# M1501B.net
KiCad netlist of a schematic drawn in EAGLE
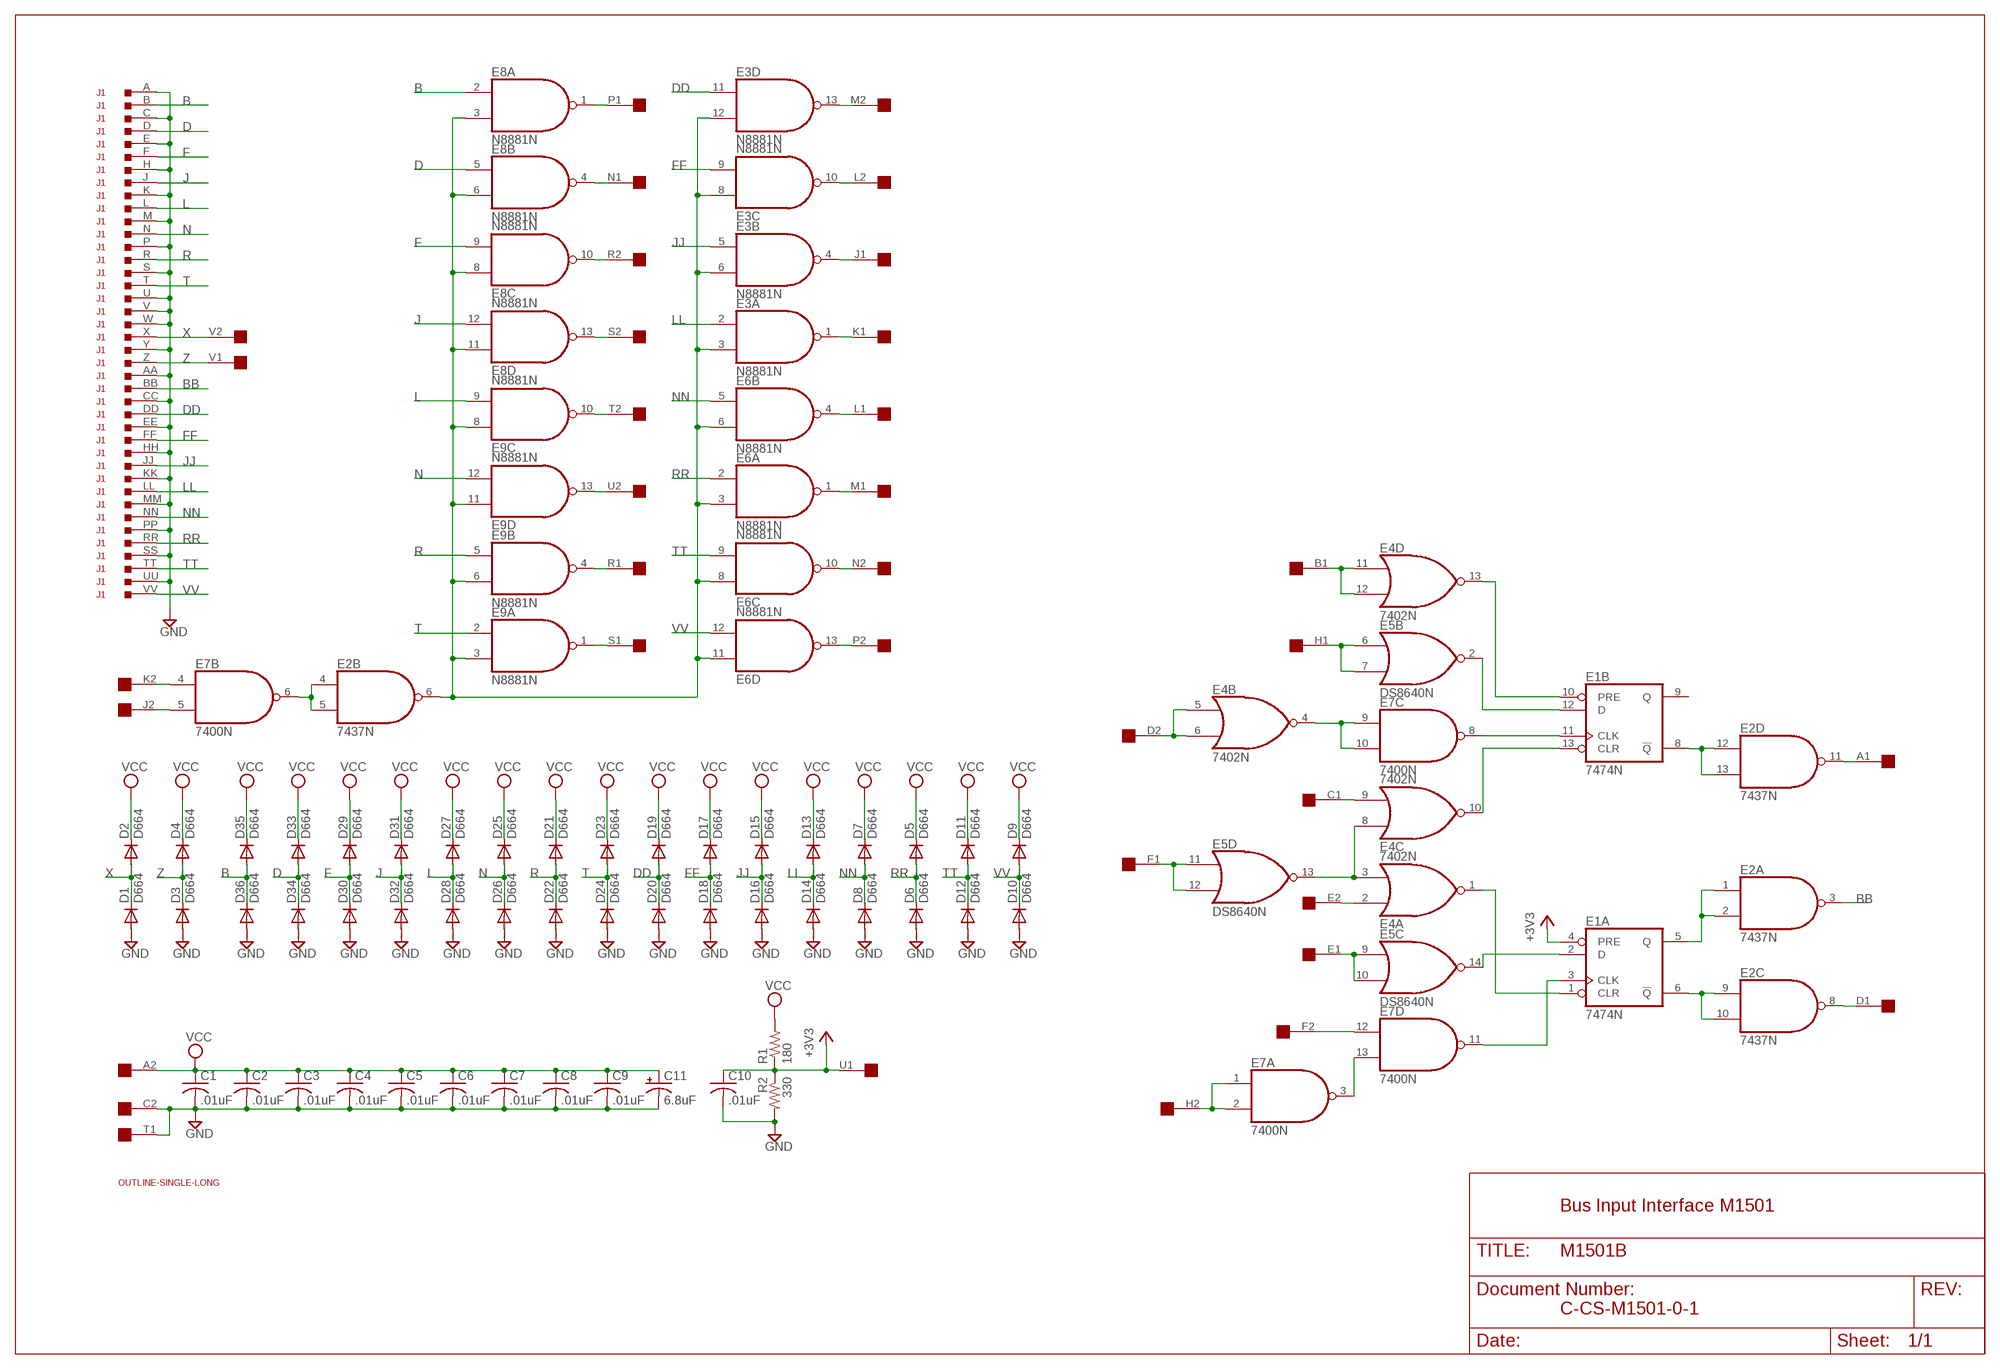
[diagram p0: schematic, sheet 1]

(export (version "E")
  (design (tool "Eeschema 10.0.6"))
  (components
    (comp (ref "C1")
      (value ".01uF")
      (footprint "eagle-import:C050-025X075")
      (libsource (lib "eagle-import") (part "C-US050-025X075"))
    )
    (comp (ref "C2")
      (value ".01uF")
      (footprint "eagle-import:C050-025X075")
      (libsource (lib "eagle-import") (part "C-US050-025X075"))
    )
    (comp (ref "C3")
      (value ".01uF")
      (footprint "eagle-import:C050-025X075")
      (libsource (lib "eagle-import") (part "C-US050-025X075"))
    )
    (comp (ref "C4")
      (value ".01uF")
      (footprint "eagle-import:C050-025X075")
      (libsource (lib "eagle-import") (part "C-US050-025X075"))
    )
    (comp (ref "C5")
      (value ".01uF")
      (footprint "eagle-import:C050-025X075")
      (libsource (lib "eagle-import") (part "C-US050-025X075"))
    )
    (comp (ref "C6")
      (value ".01uF")
      (footprint "eagle-import:C050-025X075")
      (libsource (lib "eagle-import") (part "C-US050-025X075"))
    )
    (comp (ref "C7")
      (value ".01uF")
      (footprint "eagle-import:C050-025X075")
      (libsource (lib "eagle-import") (part "C-US050-025X075"))
    )
    (comp (ref "C8")
      (value ".01uF")
      (footprint "eagle-import:C050-025X075")
      (libsource (lib "eagle-import") (part "C-US050-025X075"))
    )
    (comp (ref "C9")
      (value ".01uF")
      (footprint "eagle-import:C050-025X075")
      (libsource (lib "eagle-import") (part "C-US050-025X075"))
    )
    (comp (ref "C10")
      (value ".01uF")
      (footprint "eagle-import:C050-025X075")
      (libsource (lib "eagle-import") (part "C-US050-025X075"))
    )
    (comp (ref "C11")
      (value "6.8uF")
      (footprint "eagle-import:E12-8")
      (libsource (lib "eagle-import") (part "CPOL-USE20-8AXIAL"))
    )
    (comp (ref "D1")
      (value "D664")
      (footprint "eagle-import:DO35-10")
      (libsource (lib "eagle-import") (part "DIODE-DO35-10"))
    )
    (comp (ref "D2")
      (value "D664")
      (footprint "eagle-import:DO35-10")
      (libsource (lib "eagle-import") (part "DIODE-DO35-10"))
    )
    (comp (ref "D3")
      (value "D664")
      (footprint "eagle-import:DO35-10")
      (libsource (lib "eagle-import") (part "DIODE-DO35-10"))
    )
    (comp (ref "D4")
      (value "D664")
      (footprint "eagle-import:DO35-10")
      (libsource (lib "eagle-import") (part "DIODE-DO35-10"))
    )
    (comp (ref "D5")
      (value "D664")
      (footprint "eagle-import:DO35-10")
      (libsource (lib "eagle-import") (part "DIODE-DO35-10"))
    )
    (comp (ref "D6")
      (value "D664")
      (footprint "eagle-import:DO35-10")
      (libsource (lib "eagle-import") (part "DIODE-DO35-10"))
    )
    (comp (ref "D7")
      (value "D664")
      (footprint "eagle-import:DO35-10")
      (libsource (lib "eagle-import") (part "DIODE-DO35-10"))
    )
    (comp (ref "D8")
      (value "D664")
      (footprint "eagle-import:DO35-10")
      (libsource (lib "eagle-import") (part "DIODE-DO35-10"))
    )
    (comp (ref "D9")
      (value "D664")
      (footprint "eagle-import:DO35-10")
      (libsource (lib "eagle-import") (part "DIODE-DO35-10"))
    )
    (comp (ref "D10")
      (value "D664")
      (footprint "eagle-import:DO35-10")
      (libsource (lib "eagle-import") (part "DIODE-DO35-10"))
    )
    (comp (ref "D11")
      (value "D664")
      (footprint "eagle-import:DO35-10")
      (libsource (lib "eagle-import") (part "DIODE-DO35-10"))
    )
    (comp (ref "D12")
      (value "D664")
      (footprint "eagle-import:DO35-10")
      (libsource (lib "eagle-import") (part "DIODE-DO35-10"))
    )
    (comp (ref "D13")
      (value "D664")
      (footprint "eagle-import:DO35-10")
      (libsource (lib "eagle-import") (part "DIODE-DO35-10"))
    )
    (comp (ref "D14")
      (value "D664")
      (footprint "eagle-import:DO35-10")
      (libsource (lib "eagle-import") (part "DIODE-DO35-10"))
    )
    (comp (ref "D15")
      (value "D664")
      (footprint "eagle-import:DO35-10")
      (libsource (lib "eagle-import") (part "DIODE-DO35-10"))
    )
    (comp (ref "D16")
      (value "D664")
      (footprint "eagle-import:DO35-10")
      (libsource (lib "eagle-import") (part "DIODE-DO35-10"))
    )
    (comp (ref "D17")
      (value "D664")
      (footprint "eagle-import:DO35-10")
      (libsource (lib "eagle-import") (part "DIODE-DO35-10"))
    )
    (comp (ref "D18")
      (value "D664")
      (footprint "eagle-import:DO35-10")
      (libsource (lib "eagle-import") (part "DIODE-DO35-10"))
    )
    (comp (ref "D19")
      (value "D664")
      (footprint "eagle-import:DO35-10")
      (libsource (lib "eagle-import") (part "DIODE-DO35-10"))
    )
    (comp (ref "D20")
      (value "D664")
      (footprint "eagle-import:DO35-10")
      (libsource (lib "eagle-import") (part "DIODE-DO35-10"))
    )
    (comp (ref "D21")
      (value "D664")
      (footprint "eagle-import:DO35-10")
      (libsource (lib "eagle-import") (part "DIODE-DO35-10"))
    )
    (comp (ref "D22")
      (value "D664")
      (footprint "eagle-import:DO35-10")
      (libsource (lib "eagle-import") (part "DIODE-DO35-10"))
    )
    (comp (ref "D23")
      (value "D664")
      (footprint "eagle-import:DO35-10")
      (libsource (lib "eagle-import") (part "DIODE-DO35-10"))
    )
    (comp (ref "D24")
      (value "D664")
      (footprint "eagle-import:DO35-10")
      (libsource (lib "eagle-import") (part "DIODE-DO35-10"))
    )
    (comp (ref "D25")
      (value "D664")
      (footprint "eagle-import:DO35-10")
      (libsource (lib "eagle-import") (part "DIODE-DO35-10"))
    )
    (comp (ref "D26")
      (value "D664")
      (footprint "eagle-import:DO35-10")
      (libsource (lib "eagle-import") (part "DIODE-DO35-10"))
    )
    (comp (ref "D27")
      (value "D664")
      (footprint "eagle-import:DO35-10")
      (libsource (lib "eagle-import") (part "DIODE-DO35-10"))
    )
    (comp (ref "D28")
      (value "D664")
      (footprint "eagle-import:DO35-10")
      (libsource (lib "eagle-import") (part "DIODE-DO35-10"))
    )
    (comp (ref "D29")
      (value "D664")
      (footprint "eagle-import:DO35-10")
      (libsource (lib "eagle-import") (part "DIODE-DO35-10"))
    )
    (comp (ref "D30")
      (value "D664")
      (footprint "eagle-import:DO35-10")
      (libsource (lib "eagle-import") (part "DIODE-DO35-10"))
    )
    (comp (ref "D31")
      (value "D664")
      (footprint "eagle-import:DO35-10")
      (libsource (lib "eagle-import") (part "DIODE-DO35-10"))
    )
    (comp (ref "D32")
      (value "D664")
      (footprint "eagle-import:DO35-10")
      (libsource (lib "eagle-import") (part "DIODE-DO35-10"))
    )
    (comp (ref "D33")
      (value "D664")
      (footprint "eagle-import:DO35-10")
      (libsource (lib "eagle-import") (part "DIODE-DO35-10"))
    )
    (comp (ref "D34")
      (value "D664")
      (footprint "eagle-import:DO35-10")
      (libsource (lib "eagle-import") (part "DIODE-DO35-10"))
    )
    (comp (ref "D35")
      (value "D664")
      (footprint "eagle-import:DO35-10")
      (libsource (lib "eagle-import") (part "DIODE-DO35-10"))
    )
    (comp (ref "D36")
      (value "D664")
      (footprint "eagle-import:DO35-10")
      (libsource (lib "eagle-import") (part "DIODE-DO35-10"))
    )
    (comp (ref "E1")
      (value "7474N")
      (footprint "eagle-import:DIL14")
      (libsource (lib "eagle-import") (part "7474NS"))
    )
    (comp (ref "E2")
      (value "7437N")
      (footprint "eagle-import:DIL14")
      (libsource (lib "eagle-import") (part "7437N"))
    )
    (comp (ref "E3")
      (value "N8881N")
      (footprint "eagle-import:DIL14")
      (libsource (lib "eagle-import") (part "N8881N"))
    )
    (comp (ref "E4")
      (value "7402N")
      (footprint "eagle-import:DIL14")
      (libsource (lib "eagle-import") (part "7402N"))
    )
    (comp (ref "E5")
      (value "DS8640N")
      (footprint "eagle-import:DIL14")
      (libsource (lib "eagle-import") (part "DS8640N"))
    )
    (comp (ref "E6")
      (value "N8881N")
      (footprint "eagle-import:DIL14")
      (libsource (lib "eagle-import") (part "N8881N"))
    )
    (comp (ref "E7")
      (value "7400N")
      (footprint "eagle-import:DIL14")
      (libsource (lib "eagle-import") (part "7400N"))
    )
    (comp (ref "E8")
      (value "N8881N")
      (footprint "eagle-import:DIL14")
      (libsource (lib "eagle-import") (part "N8881N"))
    )
    (comp (ref "E9")
      (value "N8881N")
      (footprint "eagle-import:DIL14")
      (libsource (lib "eagle-import") (part "N8881N"))
    )
    (comp (ref "J1")
      (value "DEC40PINSH")
      (footprint "eagle-import:DEC40PINH")
      (libsource (lib "eagle-import") (part "DEC40PINSH"))
    )
    (comp (ref "R1")
      (value "180")
      (footprint "eagle-import:0207_10")
      (libsource (lib "eagle-import") (part "R-US_0207/10"))
    )
    (comp (ref "R2")
      (value "330")
      (footprint "eagle-import:0207_10")
      (libsource (lib "eagle-import") (part "R-US_0207/10"))
    )
    (comp (ref "U$1")
      (value "OUTLINE-SINGLE-LONG")
      (footprint "eagle-import:SINGLE-LONG")
      (libsource (lib "eagle-import") (part "OUTLINE-SINGLE-LONG"))
    )
    (comp (ref "U$2")
      (value "SINGLE")
      (footprint "eagle-import:EDGE-CON2")
      (libsource (lib "eagle-import") (part "SINGLE"))
    )
  )
  (nets
    (net (code "1") (name "+3V3") (class "Default")
      (node (ref "C10") (pin "1") (pinfunction "1_1") (pintype "passive"))
      (node (ref "E1") (pin "4") (pinfunction "PRE_4") (pintype "input"))
      (node (ref "R1") (pin "1") (pinfunction "1_1") (pintype "passive"))
      (node (ref "R2") (pin "1") (pinfunction "1_1") (pintype "passive"))
      (node (ref "U$2") (pin "U1") (pinfunction "1_U1") (pintype "bidirectional"))
    )
    (net (code "2") (name "/B") (class "Default")
      (node (ref "D35") (pin "A") (pinfunction "A_A") (pintype "passive"))
      (node (ref "D36") (pin "C") (pinfunction "C_C") (pintype "passive"))
      (node (ref "E8") (pin "2") (pinfunction "I0_2") (pintype "input"))
      (node (ref "J1") (pin "B") (pinfunction "P$2_B") (pintype "passive"))
    )
    (net (code "3") (name "/BB") (class "Default")
      (node (ref "E2") (pin "3") (pinfunction "O_3") (pintype "output"))
      (node (ref "J1") (pin "BB") (pinfunction "P$2_BB") (pintype "passive"))
    )
    (net (code "4") (name "/D") (class "Default")
      (node (ref "D33") (pin "A") (pinfunction "A_A") (pintype "passive"))
      (node (ref "D34") (pin "C") (pinfunction "C_C") (pintype "passive"))
      (node (ref "E8") (pin "5") (pinfunction "I0_5") (pintype "input"))
      (node (ref "J1") (pin "D") (pinfunction "P$2_D") (pintype "passive"))
    )
    (net (code "5") (name "/DD") (class "Default")
      (node (ref "D19") (pin "A") (pinfunction "A_A") (pintype "passive"))
      (node (ref "D20") (pin "C") (pinfunction "C_C") (pintype "passive"))
      (node (ref "E3") (pin "11") (pinfunction "I0_11") (pintype "input"))
      (node (ref "J1") (pin "DD") (pinfunction "P$2_DD") (pintype "passive"))
    )
    (net (code "6") (name "/F") (class "Default")
      (node (ref "D29") (pin "A") (pinfunction "A_A") (pintype "passive"))
      (node (ref "D30") (pin "C") (pinfunction "C_C") (pintype "passive"))
      (node (ref "E8") (pin "9") (pinfunction "I1_9") (pintype "input"))
      (node (ref "J1") (pin "F") (pinfunction "P$2_F") (pintype "passive"))
    )
    (net (code "7") (name "/FF") (class "Default")
      (node (ref "D17") (pin "A") (pinfunction "A_A") (pintype "passive"))
      (node (ref "D18") (pin "C") (pinfunction "C_C") (pintype "passive"))
      (node (ref "E3") (pin "9") (pinfunction "I1_9") (pintype "input"))
      (node (ref "J1") (pin "FF") (pinfunction "P$2_FF") (pintype "passive"))
    )
    (net (code "8") (name "/J") (class "Default")
      (node (ref "D31") (pin "A") (pinfunction "A_A") (pintype "passive"))
      (node (ref "D32") (pin "C") (pinfunction "C_C") (pintype "passive"))
      (node (ref "E8") (pin "12") (pinfunction "I1_12") (pintype "input"))
      (node (ref "J1") (pin "J") (pinfunction "P$2_J") (pintype "passive"))
    )
    (net (code "9") (name "/JJ") (class "Default")
      (node (ref "D15") (pin "A") (pinfunction "A_A") (pintype "passive"))
      (node (ref "D16") (pin "C") (pinfunction "C_C") (pintype "passive"))
      (node (ref "E3") (pin "5") (pinfunction "I0_5") (pintype "input"))
      (node (ref "J1") (pin "JJ") (pinfunction "P$2_JJ") (pintype "passive"))
    )
    (net (code "10") (name "/L") (class "Default")
      (node (ref "D27") (pin "A") (pinfunction "A_A") (pintype "passive"))
      (node (ref "D28") (pin "C") (pinfunction "C_C") (pintype "passive"))
      (node (ref "E9") (pin "9") (pinfunction "I1_9") (pintype "input"))
      (node (ref "J1") (pin "L") (pinfunction "P$2_L") (pintype "passive"))
    )
    (net (code "11") (name "/LL") (class "Default")
      (node (ref "D13") (pin "A") (pinfunction "A_A") (pintype "passive"))
      (node (ref "D14") (pin "C") (pinfunction "C_C") (pintype "passive"))
      (node (ref "E3") (pin "2") (pinfunction "I0_2") (pintype "input"))
      (node (ref "J1") (pin "LL") (pinfunction "P$2_LL") (pintype "passive"))
    )
    (net (code "12") (name "/N") (class "Default")
      (node (ref "D25") (pin "A") (pinfunction "A_A") (pintype "passive"))
      (node (ref "D26") (pin "C") (pinfunction "C_C") (pintype "passive"))
      (node (ref "E9") (pin "12") (pinfunction "I1_12") (pintype "input"))
      (node (ref "J1") (pin "N") (pinfunction "P$2_N") (pintype "passive"))
    )
    (net (code "13") (name "/NN") (class "Default")
      (node (ref "D7") (pin "A") (pinfunction "A_A") (pintype "passive"))
      (node (ref "D8") (pin "C") (pinfunction "C_C") (pintype "passive"))
      (node (ref "E6") (pin "5") (pinfunction "I0_5") (pintype "input"))
      (node (ref "J1") (pin "NN") (pinfunction "P$2_NN") (pintype "passive"))
    )
    (net (code "14") (name "/R") (class "Default")
      (node (ref "D21") (pin "A") (pinfunction "A_A") (pintype "passive"))
      (node (ref "D22") (pin "C") (pinfunction "C_C") (pintype "passive"))
      (node (ref "E9") (pin "5") (pinfunction "I0_5") (pintype "input"))
      (node (ref "J1") (pin "R") (pinfunction "P$2_R") (pintype "passive"))
    )
    (net (code "15") (name "/RR") (class "Default")
      (node (ref "D5") (pin "A") (pinfunction "A_A") (pintype "passive"))
      (node (ref "D6") (pin "C") (pinfunction "C_C") (pintype "passive"))
      (node (ref "E6") (pin "2") (pinfunction "I0_2") (pintype "input"))
      (node (ref "J1") (pin "RR") (pinfunction "P$2_RR") (pintype "passive"))
    )
    (net (code "16") (name "/T") (class "Default")
      (node (ref "D23") (pin "A") (pinfunction "A_A") (pintype "passive"))
      (node (ref "D24") (pin "C") (pinfunction "C_C") (pintype "passive"))
      (node (ref "E9") (pin "2") (pinfunction "I0_2") (pintype "input"))
      (node (ref "J1") (pin "T") (pinfunction "P$2_T") (pintype "passive"))
    )
    (net (code "17") (name "/TT") (class "Default")
      (node (ref "D11") (pin "A") (pinfunction "A_A") (pintype "passive"))
      (node (ref "D12") (pin "C") (pinfunction "C_C") (pintype "passive"))
      (node (ref "E6") (pin "9") (pinfunction "I1_9") (pintype "input"))
      (node (ref "J1") (pin "TT") (pinfunction "P$2_TT") (pintype "passive"))
    )
    (net (code "18") (name "/VV") (class "Default")
      (node (ref "D10") (pin "C") (pinfunction "C_C") (pintype "passive"))
      (node (ref "D9") (pin "A") (pinfunction "A_A") (pintype "passive"))
      (node (ref "E6") (pin "12") (pinfunction "I1_12") (pintype "input"))
      (node (ref "J1") (pin "VV") (pinfunction "P$2_VV") (pintype "passive"))
    )
    (net (code "19") (name "/X") (class "Default")
      (node (ref "D1") (pin "C") (pinfunction "C_C") (pintype "passive"))
      (node (ref "D2") (pin "A") (pinfunction "A_A") (pintype "passive"))
      (node (ref "J1") (pin "X") (pinfunction "P$2_X") (pintype "passive"))
      (node (ref "U$2") (pin "V2") (pinfunction "1_V2") (pintype "bidirectional"))
    )
    (net (code "20") (name "/Z") (class "Default")
      (node (ref "D3") (pin "C") (pinfunction "C_C") (pintype "passive"))
      (node (ref "D4") (pin "A") (pinfunction "A_A") (pintype "passive"))
      (node (ref "J1") (pin "Z") (pinfunction "P$2_Z") (pintype "passive"))
      (node (ref "U$2") (pin "V1") (pinfunction "1_V1") (pintype "bidirectional"))
    )
    (net (code "21") (name "GND") (class "Default")
      (node (ref "C1") (pin "2") (pinfunction "2_2") (pintype "passive"))
      (node (ref "C10") (pin "2") (pinfunction "2_2") (pintype "passive"))
      (node (ref "C11") (pin "-") (pinfunction "-_-") (pintype "passive"))
      (node (ref "C2") (pin "2") (pinfunction "2_2") (pintype "passive"))
      (node (ref "C3") (pin "2") (pinfunction "2_2") (pintype "passive"))
      (node (ref "C4") (pin "2") (pinfunction "2_2") (pintype "passive"))
      (node (ref "C5") (pin "2") (pinfunction "2_2") (pintype "passive"))
      (node (ref "C6") (pin "2") (pinfunction "2_2") (pintype "passive"))
      (node (ref "C7") (pin "2") (pinfunction "2_2") (pintype "passive"))
      (node (ref "C8") (pin "2") (pinfunction "2_2") (pintype "passive"))
      (node (ref "C9") (pin "2") (pinfunction "2_2") (pintype "passive"))
      (node (ref "D1") (pin "A") (pinfunction "A_A") (pintype "passive"))
      (node (ref "D10") (pin "A") (pinfunction "A_A") (pintype "passive"))
      (node (ref "D12") (pin "A") (pinfunction "A_A") (pintype "passive"))
      (node (ref "D14") (pin "A") (pinfunction "A_A") (pintype "passive"))
      (node (ref "D16") (pin "A") (pinfunction "A_A") (pintype "passive"))
      (node (ref "D18") (pin "A") (pinfunction "A_A") (pintype "passive"))
      (node (ref "D20") (pin "A") (pinfunction "A_A") (pintype "passive"))
      (node (ref "D22") (pin "A") (pinfunction "A_A") (pintype "passive"))
      (node (ref "D24") (pin "A") (pinfunction "A_A") (pintype "passive"))
      (node (ref "D26") (pin "A") (pinfunction "A_A") (pintype "passive"))
      (node (ref "D28") (pin "A") (pinfunction "A_A") (pintype "passive"))
      (node (ref "D3") (pin "A") (pinfunction "A_A") (pintype "passive"))
      (node (ref "D30") (pin "A") (pinfunction "A_A") (pintype "passive"))
      (node (ref "D32") (pin "A") (pinfunction "A_A") (pintype "passive"))
      (node (ref "D34") (pin "A") (pinfunction "A_A") (pintype "passive"))
      (node (ref "D36") (pin "A") (pinfunction "A_A") (pintype "passive"))
      (node (ref "D6") (pin "A") (pinfunction "A_A") (pintype "passive"))
      (node (ref "D8") (pin "A") (pinfunction "A_A") (pintype "passive"))
      (node (ref "J1") (pin "A") (pinfunction "P$2_A") (pintype "passive"))
      (node (ref "J1") (pin "AA") (pinfunction "P$2_AA") (pintype "passive"))
      (node (ref "J1") (pin "C") (pinfunction "P$2_C") (pintype "passive"))
      (node (ref "J1") (pin "CC") (pinfunction "P$2_CC") (pintype "passive"))
      (node (ref "J1") (pin "E") (pinfunction "P$2_E") (pintype "passive"))
      (node (ref "J1") (pin "EE") (pinfunction "P$2_EE") (pintype "passive"))
      (node (ref "J1") (pin "H") (pinfunction "P$2_H") (pintype "passive"))
      (node (ref "J1") (pin "HH") (pinfunction "P$2_HH") (pintype "passive"))
      (node (ref "J1") (pin "K") (pinfunction "P$2_K") (pintype "passive"))
      (node (ref "J1") (pin "KK") (pinfunction "P$2_KK") (pintype "passive"))
      (node (ref "J1") (pin "M") (pinfunction "P$2_M") (pintype "passive"))
      (node (ref "J1") (pin "MM") (pinfunction "P$2_MM") (pintype "passive"))
      (node (ref "J1") (pin "P") (pinfunction "P$2_P") (pintype "passive"))
      (node (ref "J1") (pin "PP") (pinfunction "P$2_PP") (pintype "passive"))
      (node (ref "J1") (pin "S") (pinfunction "P$2_S") (pintype "passive"))
      (node (ref "J1") (pin "SS") (pinfunction "P$2_SS") (pintype "passive"))
      (node (ref "J1") (pin "U") (pinfunction "P$2_U") (pintype "passive"))
      (node (ref "J1") (pin "UU") (pinfunction "P$2_UU") (pintype "passive"))
      (node (ref "J1") (pin "V") (pinfunction "P$2_V") (pintype "passive"))
      (node (ref "J1") (pin "W") (pinfunction "P$2_W") (pintype "passive"))
      (node (ref "J1") (pin "Y") (pinfunction "P$2_Y") (pintype "passive"))
      (node (ref "R2") (pin "2") (pinfunction "2_2") (pintype "passive"))
      (node (ref "U$2") (pin "C2") (pinfunction "1_C2") (pintype "bidirectional"))
      (node (ref "U$2") (pin "T1") (pinfunction "1_T1") (pintype "bidirectional"))
    )
    (net (code "22") (name "Net-(E1A-CLK)") (class "Default")
      (node (ref "E1") (pin "3") (pinfunction "CLK_3") (pintype "input"))
      (node (ref "E7") (pin "11") (pinfunction "O_11") (pintype "output"))
    )
    (net (code "23") (name "Net-(E1A-CLR)") (class "Default")
      (node (ref "E1") (pin "1") (pinfunction "CLR_1") (pintype "input"))
      (node (ref "E4") (pin "1") (pinfunction "O_1") (pintype "output"))
    )
    (net (code "24") (name "Net-(E1A-D)") (class "Default")
      (node (ref "E1") (pin "2") (pinfunction "D_2") (pintype "input"))
      (node (ref "E5") (pin "14") (pinfunction "O_14") (pintype "output"))
    )
    (net (code "25") (name "Net-(E1A-Q)") (class "Default")
      (node (ref "E1") (pin "5") (pinfunction "Q_5") (pintype "output"))
      (node (ref "E2") (pin "1") (pinfunction "I0_1") (pintype "input"))
      (node (ref "E2") (pin "2") (pinfunction "I1_2") (pintype "input"))
    )
    (net (code "26") (name "Net-(E1A-~{Q})") (class "Default")
      (node (ref "E1") (pin "6") (pinfunction "~{Q}_6") (pintype "output"))
      (node (ref "E2") (pin "10") (pinfunction "I1_10") (pintype "input"))
      (node (ref "E2") (pin "9") (pinfunction "I0_9") (pintype "input"))
    )
    (net (code "27") (name "Net-(E1B-CLK)") (class "Default")
      (node (ref "E1") (pin "11") (pinfunction "CLK_11") (pintype "input"))
      (node (ref "E7") (pin "8") (pinfunction "O_8") (pintype "output"))
    )
    (net (code "28") (name "Net-(E1B-CLR)") (class "Default")
      (node (ref "E1") (pin "13") (pinfunction "CLR_13") (pintype "input"))
      (node (ref "E4") (pin "10") (pinfunction "O_10") (pintype "output"))
    )
    (net (code "29") (name "Net-(E1B-D)") (class "Default")
      (node (ref "E1") (pin "12") (pinfunction "D_12") (pintype "input"))
      (node (ref "E5") (pin "2") (pinfunction "O_2") (pintype "output"))
    )
    (net (code "30") (name "Net-(E1B-PRE)") (class "Default")
      (node (ref "E1") (pin "10") (pinfunction "PRE_10") (pintype "input"))
      (node (ref "E4") (pin "13") (pinfunction "O_13") (pintype "output"))
    )
    (net (code "31") (name "Net-(E1B-~{Q})") (class "Default")
      (node (ref "E1") (pin "8") (pinfunction "~{Q}_8") (pintype "output"))
      (node (ref "E2") (pin "12") (pinfunction "I0_12") (pintype "input"))
      (node (ref "E2") (pin "13") (pinfunction "I1_13") (pintype "input"))
    )
    (net (code "32") (name "Net-(E2B-I0)") (class "Default")
      (node (ref "E2") (pin "4") (pinfunction "I0_4") (pintype "input"))
      (node (ref "E2") (pin "5") (pinfunction "I1_5") (pintype "input"))
      (node (ref "E7") (pin "6") (pinfunction "O_6") (pintype "output"))
    )
    (net (code "33") (name "Net-(E2B-O)") (class "Default")
      (node (ref "E2") (pin "6") (pinfunction "O_6") (pintype "output"))
      (node (ref "E3") (pin "12") (pinfunction "I1_12") (pintype "input"))
      (node (ref "E3") (pin "3") (pinfunction "I1_3") (pintype "input"))
      (node (ref "E3") (pin "6") (pinfunction "I1_6") (pintype "input"))
      (node (ref "E3") (pin "8") (pinfunction "I0_8") (pintype "input"))
      (node (ref "E6") (pin "11") (pinfunction "I0_11") (pintype "input"))
      (node (ref "E6") (pin "3") (pinfunction "I1_3") (pintype "input"))
      (node (ref "E6") (pin "6") (pinfunction "I1_6") (pintype "input"))
      (node (ref "E6") (pin "8") (pinfunction "I0_8") (pintype "input"))
      (node (ref "E8") (pin "11") (pinfunction "I0_11") (pintype "input"))
      (node (ref "E8") (pin "3") (pinfunction "I1_3") (pintype "input"))
      (node (ref "E8") (pin "6") (pinfunction "I1_6") (pintype "input"))
      (node (ref "E8") (pin "8") (pinfunction "I0_8") (pintype "input"))
      (node (ref "E9") (pin "11") (pinfunction "I0_11") (pintype "input"))
      (node (ref "E9") (pin "3") (pinfunction "I1_3") (pintype "input"))
      (node (ref "E9") (pin "6") (pinfunction "I1_6") (pintype "input"))
      (node (ref "E9") (pin "8") (pinfunction "I0_8") (pintype "input"))
    )
    (net (code "34") (name "Net-(E2C-O)") (class "Default")
      (node (ref "E2") (pin "8") (pinfunction "O_8") (pintype "output"))
      (node (ref "U$2") (pin "D1") (pinfunction "1_D1") (pintype "bidirectional"))
    )
    (net (code "35") (name "Net-(E2D-O)") (class "Default")
      (node (ref "E2") (pin "11") (pinfunction "O_11") (pintype "output"))
      (node (ref "U$2") (pin "A1") (pinfunction "1_A1") (pintype "bidirectional"))
    )
    (net (code "36") (name "Net-(E3A-O)") (class "Default")
      (node (ref "E3") (pin "1") (pinfunction "O_1") (pintype "open_collector"))
      (node (ref "U$2") (pin "K1") (pinfunction "1_K1") (pintype "bidirectional"))
    )
    (net (code "37") (name "Net-(E3B-O)") (class "Default")
      (node (ref "E3") (pin "4") (pinfunction "O_4") (pintype "open_collector"))
      (node (ref "U$2") (pin "J1") (pinfunction "1_J1") (pintype "bidirectional"))
    )
    (net (code "38") (name "Net-(E3C-O)") (class "Default")
      (node (ref "E3") (pin "10") (pinfunction "O_10") (pintype "open_collector"))
      (node (ref "U$2") (pin "L2") (pinfunction "1_L2") (pintype "bidirectional"))
    )
    (net (code "39") (name "Net-(E3D-O)") (class "Default")
      (node (ref "E3") (pin "13") (pinfunction "O_13") (pintype "open_collector"))
      (node (ref "U$2") (pin "M2") (pinfunction "1_M2") (pintype "bidirectional"))
    )
    (net (code "40") (name "Net-(E4A-I0)") (class "Default")
      (node (ref "E4") (pin "2") (pinfunction "I0_2") (pintype "input"))
      (node (ref "U$2") (pin "E2") (pinfunction "1_E2") (pintype "bidirectional"))
    )
    (net (code "41") (name "Net-(E4A-I1)") (class "Default")
      (node (ref "E4") (pin "3") (pinfunction "I1_3") (pintype "input"))
      (node (ref "E4") (pin "8") (pinfunction "I0_8") (pintype "input"))
      (node (ref "E5") (pin "13") (pinfunction "O_13") (pintype "output"))
    )
    (net (code "42") (name "Net-(E4B-I0)") (class "Default")
      (node (ref "E4") (pin "5") (pinfunction "I0_5") (pintype "input"))
      (node (ref "E4") (pin "6") (pinfunction "I1_6") (pintype "input"))
      (node (ref "U$2") (pin "D2") (pinfunction "1_D2") (pintype "bidirectional"))
    )
    (net (code "43") (name "Net-(E4B-O)") (class "Default")
      (node (ref "E4") (pin "4") (pinfunction "O_4") (pintype "output"))
      (node (ref "E7") (pin "10") (pinfunction "I1_10") (pintype "input"))
      (node (ref "E7") (pin "9") (pinfunction "I0_9") (pintype "input"))
    )
    (net (code "44") (name "Net-(E4C-I1)") (class "Default")
      (node (ref "E4") (pin "9") (pinfunction "I1_9") (pintype "input"))
      (node (ref "U$2") (pin "C1") (pinfunction "1_C1") (pintype "bidirectional"))
    )
    (net (code "45") (name "Net-(E4D-I0)") (class "Default")
      (node (ref "E4") (pin "11") (pinfunction "I0_11") (pintype "input"))
      (node (ref "E4") (pin "12") (pinfunction "I1_12") (pintype "input"))
      (node (ref "U$2") (pin "B1") (pinfunction "1_B1") (pintype "bidirectional"))
    )
    (net (code "46") (name "Net-(E5B-I0)") (class "Default")
      (node (ref "E5") (pin "6") (pinfunction "I0_6") (pintype "input"))
      (node (ref "E5") (pin "7") (pinfunction "I1_7") (pintype "input"))
      (node (ref "U$2") (pin "H1") (pinfunction "1_H1") (pintype "bidirectional"))
    )
    (net (code "47") (name "Net-(E5C-I0)") (class "Default")
      (node (ref "E5") (pin "10") (pinfunction "I1_10") (pintype "input"))
      (node (ref "E5") (pin "9") (pinfunction "I0_9") (pintype "input"))
      (node (ref "U$2") (pin "E1") (pinfunction "1_E1") (pintype "bidirectional"))
    )
    (net (code "48") (name "Net-(E5D-I0)") (class "Default")
      (node (ref "E5") (pin "11") (pinfunction "I0_11") (pintype "input"))
      (node (ref "E5") (pin "12") (pinfunction "I1_12") (pintype "input"))
      (node (ref "U$2") (pin "F1") (pinfunction "1_F1") (pintype "bidirectional"))
    )
    (net (code "49") (name "Net-(E6A-O)") (class "Default")
      (node (ref "E6") (pin "1") (pinfunction "O_1") (pintype "open_collector"))
      (node (ref "U$2") (pin "M1") (pinfunction "1_M1") (pintype "bidirectional"))
    )
    (net (code "50") (name "Net-(E6B-O)") (class "Default")
      (node (ref "E6") (pin "4") (pinfunction "O_4") (pintype "open_collector"))
      (node (ref "U$2") (pin "L1") (pinfunction "1_L1") (pintype "bidirectional"))
    )
    (net (code "51") (name "Net-(E6C-O)") (class "Default")
      (node (ref "E6") (pin "10") (pinfunction "O_10") (pintype "open_collector"))
      (node (ref "U$2") (pin "N2") (pinfunction "1_N2") (pintype "bidirectional"))
    )
    (net (code "52") (name "Net-(E6D-O)") (class "Default")
      (node (ref "E6") (pin "13") (pinfunction "O_13") (pintype "open_collector"))
      (node (ref "U$2") (pin "P2") (pinfunction "1_P2") (pintype "bidirectional"))
    )
    (net (code "53") (name "Net-(E7A-I0)") (class "Default")
      (node (ref "E7") (pin "1") (pinfunction "I0_1") (pintype "input"))
      (node (ref "E7") (pin "2") (pinfunction "I1_2") (pintype "input"))
      (node (ref "U$2") (pin "H2") (pinfunction "1_H2") (pintype "bidirectional"))
    )
    (net (code "54") (name "Net-(E7A-O)") (class "Default")
      (node (ref "E7") (pin "13") (pinfunction "I1_13") (pintype "input"))
      (node (ref "E7") (pin "3") (pinfunction "O_3") (pintype "output"))
    )
    (net (code "55") (name "Net-(E7B-I0)") (class "Default")
      (node (ref "E7") (pin "4") (pinfunction "I0_4") (pintype "input"))
      (node (ref "U$2") (pin "K2") (pinfunction "1_K2") (pintype "bidirectional"))
    )
    (net (code "56") (name "Net-(E7B-I1)") (class "Default")
      (node (ref "E7") (pin "5") (pinfunction "I1_5") (pintype "input"))
      (node (ref "U$2") (pin "J2") (pinfunction "1_J2") (pintype "bidirectional"))
    )
    (net (code "57") (name "Net-(E7D-I0)") (class "Default")
      (node (ref "E7") (pin "12") (pinfunction "I0_12") (pintype "input"))
      (node (ref "U$2") (pin "F2") (pinfunction "1_F2") (pintype "bidirectional"))
    )
    (net (code "58") (name "Net-(E8A-O)") (class "Default")
      (node (ref "E8") (pin "1") (pinfunction "O_1") (pintype "open_collector"))
      (node (ref "U$2") (pin "P1") (pinfunction "1_P1") (pintype "bidirectional"))
    )
    (net (code "59") (name "Net-(E8B-O)") (class "Default")
      (node (ref "E8") (pin "4") (pinfunction "O_4") (pintype "open_collector"))
      (node (ref "U$2") (pin "N1") (pinfunction "1_N1") (pintype "bidirectional"))
    )
    (net (code "60") (name "Net-(E8C-O)") (class "Default")
      (node (ref "E8") (pin "10") (pinfunction "O_10") (pintype "open_collector"))
      (node (ref "U$2") (pin "R2") (pinfunction "1_R2") (pintype "bidirectional"))
    )
    (net (code "61") (name "Net-(E8D-O)") (class "Default")
      (node (ref "E8") (pin "13") (pinfunction "O_13") (pintype "open_collector"))
      (node (ref "U$2") (pin "S2") (pinfunction "1_S2") (pintype "bidirectional"))
    )
    (net (code "62") (name "Net-(E9A-O)") (class "Default")
      (node (ref "E9") (pin "1") (pinfunction "O_1") (pintype "open_collector"))
      (node (ref "U$2") (pin "S1") (pinfunction "1_S1") (pintype "bidirectional"))
    )
    (net (code "63") (name "Net-(E9B-O)") (class "Default")
      (node (ref "E9") (pin "4") (pinfunction "O_4") (pintype "open_collector"))
      (node (ref "U$2") (pin "R1") (pinfunction "1_R1") (pintype "bidirectional"))
    )
    (net (code "64") (name "Net-(E9C-O)") (class "Default")
      (node (ref "E9") (pin "10") (pinfunction "O_10") (pintype "open_collector"))
      (node (ref "U$2") (pin "T2") (pinfunction "1_T2") (pintype "bidirectional"))
    )
    (net (code "65") (name "Net-(E9D-O)") (class "Default")
      (node (ref "E9") (pin "13") (pinfunction "O_13") (pintype "open_collector"))
      (node (ref "U$2") (pin "U2") (pinfunction "1_U2") (pintype "bidirectional"))
    )
    (net (code "66") (name "VCC") (class "Default")
      (node (ref "C1") (pin "1") (pinfunction "1_1") (pintype "passive"))
      (node (ref "C11") (pin "+") (pinfunction "+_+") (pintype "passive"))
      (node (ref "C2") (pin "1") (pinfunction "1_1") (pintype "passive"))
      (node (ref "C3") (pin "1") (pinfunction "1_1") (pintype "passive"))
      (node (ref "C4") (pin "1") (pinfunction "1_1") (pintype "passive"))
      (node (ref "C5") (pin "1") (pinfunction "1_1") (pintype "passive"))
      (node (ref "C6") (pin "1") (pinfunction "1_1") (pintype "passive"))
      (node (ref "C7") (pin "1") (pinfunction "1_1") (pintype "passive"))
      (node (ref "C8") (pin "1") (pinfunction "1_1") (pintype "passive"))
      (node (ref "C9") (pin "1") (pinfunction "1_1") (pintype "passive"))
      (node (ref "D11") (pin "C") (pinfunction "C_C") (pintype "passive"))
      (node (ref "D13") (pin "C") (pinfunction "C_C") (pintype "passive"))
      (node (ref "D15") (pin "C") (pinfunction "C_C") (pintype "passive"))
      (node (ref "D17") (pin "C") (pinfunction "C_C") (pintype "passive"))
      (node (ref "D19") (pin "C") (pinfunction "C_C") (pintype "passive"))
      (node (ref "D2") (pin "C") (pinfunction "C_C") (pintype "passive"))
      (node (ref "D21") (pin "C") (pinfunction "C_C") (pintype "passive"))
      (node (ref "D23") (pin "C") (pinfunction "C_C") (pintype "passive"))
      (node (ref "D25") (pin "C") (pinfunction "C_C") (pintype "passive"))
      (node (ref "D27") (pin "C") (pinfunction "C_C") (pintype "passive"))
      (node (ref "D29") (pin "C") (pinfunction "C_C") (pintype "passive"))
      (node (ref "D31") (pin "C") (pinfunction "C_C") (pintype "passive"))
      (node (ref "D33") (pin "C") (pinfunction "C_C") (pintype "passive"))
      (node (ref "D35") (pin "C") (pinfunction "C_C") (pintype "passive"))
      (node (ref "D4") (pin "C") (pinfunction "C_C") (pintype "passive"))
      (node (ref "D5") (pin "C") (pinfunction "C_C") (pintype "passive"))
      (node (ref "D7") (pin "C") (pinfunction "C_C") (pintype "passive"))
      (node (ref "D9") (pin "C") (pinfunction "C_C") (pintype "passive"))
      (node (ref "R1") (pin "2") (pinfunction "2_2") (pintype "passive"))
      (node (ref "U$2") (pin "A2") (pinfunction "1_A2") (pintype "bidirectional"))
    )
    (net (code "67") (name "unconnected-(E1B-Q-Pad9)") (class "Default")
      (node (ref "E1") (pin "9") (pinfunction "Q_9") (pintype "output"))
    )
  )
)
